# RX_FlexiConnectors.net
KiCad netlist of a schematic drawn in Altium Designer
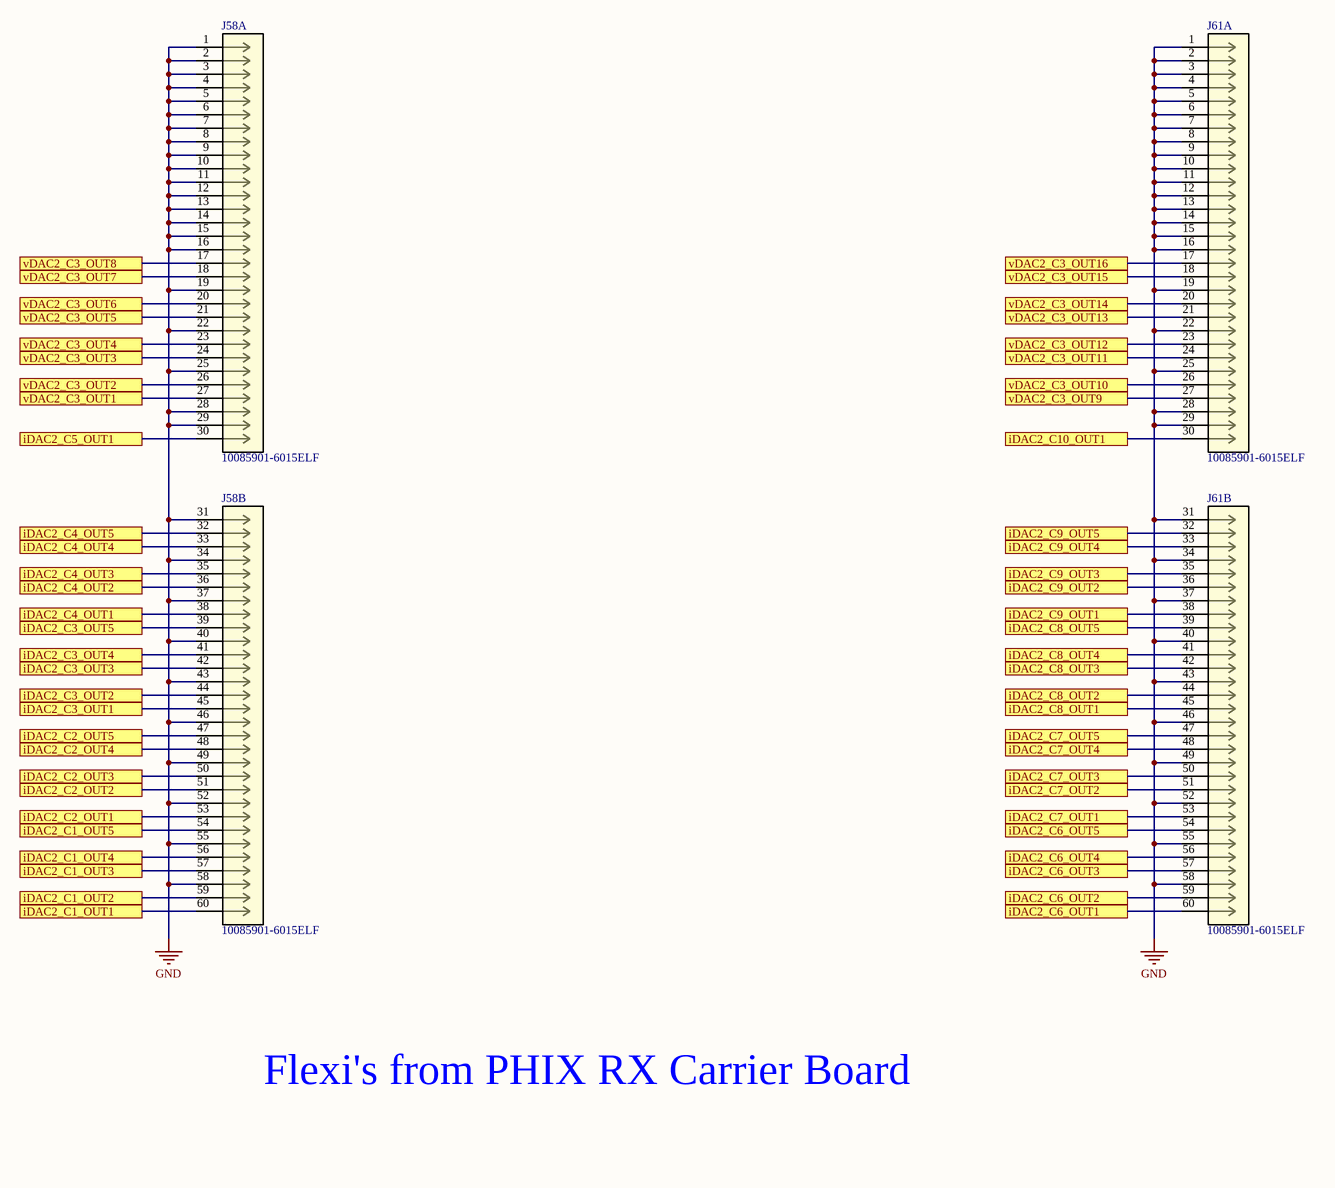
[diagram p0: RX_FlexiConnectors.SchDoc]

(export (version "E")
  (design (tool "Eeschema 10.0.6"))
  (components
    (comp (ref "J58")
      (value "10085901-6015ELF")
      (footprint "CONN_10085901-6015ELF_AMP")
      (description "No Description Available")
      (fields (field (name "COPYRIGHT") "Copyright (C) 2018 Accelerated Designs. All rights reserved"))
      (libsource (lib "PHIX-Carrier-NoDrivers") (part "10085901-6015ELF"))
    )
    (comp (ref "J61")
      (value "10085901-6015ELF")
      (footprint "CONN_10085901-6015ELF_AMP")
      (description "No Description Available")
      (fields (field (name "COPYRIGHT") "Copyright (C) 2018 Accelerated Designs. All rights reserved"))
      (libsource (lib "PHIX-Carrier-NoDrivers") (part "10085901-6015ELF"))
    )
  )
  (nets
    (net (code "1") (name "/iDAC2_C1_OUT1") (class "Default")
      (node (ref "J58") (pin "60") (pinfunction "60_60") (pintype "passive"))
    )
    (net (code "2") (name "/iDAC2_C1_OUT2") (class "Default")
      (node (ref "J58") (pin "59") (pinfunction "59_59") (pintype "passive"))
    )
    (net (code "3") (name "/iDAC2_C1_OUT3") (class "Default")
      (node (ref "J58") (pin "57") (pinfunction "57_57") (pintype "passive"))
    )
    (net (code "4") (name "/iDAC2_C1_OUT4") (class "Default")
      (node (ref "J58") (pin "56") (pinfunction "56_56") (pintype "passive"))
    )
    (net (code "5") (name "/iDAC2_C1_OUT5") (class "Default")
      (node (ref "J58") (pin "54") (pinfunction "54_54") (pintype "passive"))
    )
    (net (code "6") (name "/iDAC2_C2_OUT1") (class "Default")
      (node (ref "J58") (pin "53") (pinfunction "53_53") (pintype "passive"))
    )
    (net (code "7") (name "/iDAC2_C2_OUT2") (class "Default")
      (node (ref "J58") (pin "51") (pinfunction "51_51") (pintype "passive"))
    )
    (net (code "8") (name "/iDAC2_C2_OUT3") (class "Default")
      (node (ref "J58") (pin "50") (pinfunction "50_50") (pintype "passive"))
    )
    (net (code "9") (name "/iDAC2_C2_OUT4") (class "Default")
      (node (ref "J58") (pin "48") (pinfunction "48_48") (pintype "passive"))
    )
    (net (code "10") (name "/iDAC2_C2_OUT5") (class "Default")
      (node (ref "J58") (pin "47") (pinfunction "47_47") (pintype "passive"))
    )
    (net (code "11") (name "/iDAC2_C3_OUT1") (class "Default")
      (node (ref "J58") (pin "45") (pinfunction "45_45") (pintype "passive"))
    )
    (net (code "12") (name "/iDAC2_C3_OUT2") (class "Default")
      (node (ref "J58") (pin "44") (pinfunction "44_44") (pintype "passive"))
    )
    (net (code "13") (name "/iDAC2_C3_OUT3") (class "Default")
      (node (ref "J58") (pin "42") (pinfunction "42_42") (pintype "passive"))
    )
    (net (code "14") (name "/iDAC2_C3_OUT4") (class "Default")
      (node (ref "J58") (pin "41") (pinfunction "41_41") (pintype "passive"))
    )
    (net (code "15") (name "/iDAC2_C3_OUT5") (class "Default")
      (node (ref "J58") (pin "39") (pinfunction "39_39") (pintype "passive"))
    )
    (net (code "16") (name "/iDAC2_C4_OUT1") (class "Default")
      (node (ref "J58") (pin "38") (pinfunction "38_38") (pintype "passive"))
    )
    (net (code "17") (name "/iDAC2_C4_OUT2") (class "Default")
      (node (ref "J58") (pin "36") (pinfunction "36_36") (pintype "passive"))
    )
    (net (code "18") (name "/iDAC2_C4_OUT3") (class "Default")
      (node (ref "J58") (pin "35") (pinfunction "35_35") (pintype "passive"))
    )
    (net (code "19") (name "/iDAC2_C4_OUT4") (class "Default")
      (node (ref "J58") (pin "33") (pinfunction "33_33") (pintype "passive"))
    )
    (net (code "20") (name "/iDAC2_C4_OUT5") (class "Default")
      (node (ref "J58") (pin "32") (pinfunction "32_32") (pintype "passive"))
    )
    (net (code "21") (name "/iDAC2_C5_OUT1") (class "Default")
      (node (ref "J58") (pin "30") (pinfunction "30_30") (pintype "passive"))
    )
    (net (code "22") (name "/iDAC2_C6_OUT1") (class "Default")
      (node (ref "J61") (pin "60") (pinfunction "60_60") (pintype "passive"))
    )
    (net (code "23") (name "/iDAC2_C6_OUT2") (class "Default")
      (node (ref "J61") (pin "59") (pinfunction "59_59") (pintype "passive"))
    )
    (net (code "24") (name "/iDAC2_C6_OUT3") (class "Default")
      (node (ref "J61") (pin "57") (pinfunction "57_57") (pintype "passive"))
    )
    (net (code "25") (name "/iDAC2_C6_OUT4") (class "Default")
      (node (ref "J61") (pin "56") (pinfunction "56_56") (pintype "passive"))
    )
    (net (code "26") (name "/iDAC2_C6_OUT5") (class "Default")
      (node (ref "J61") (pin "54") (pinfunction "54_54") (pintype "passive"))
    )
    (net (code "27") (name "/iDAC2_C7_OUT1") (class "Default")
      (node (ref "J61") (pin "53") (pinfunction "53_53") (pintype "passive"))
    )
    (net (code "28") (name "/iDAC2_C7_OUT2") (class "Default")
      (node (ref "J61") (pin "51") (pinfunction "51_51") (pintype "passive"))
    )
    (net (code "29") (name "/iDAC2_C7_OUT3") (class "Default")
      (node (ref "J61") (pin "50") (pinfunction "50_50") (pintype "passive"))
    )
    (net (code "30") (name "/iDAC2_C7_OUT4") (class "Default")
      (node (ref "J61") (pin "48") (pinfunction "48_48") (pintype "passive"))
    )
    (net (code "31") (name "/iDAC2_C7_OUT5") (class "Default")
      (node (ref "J61") (pin "47") (pinfunction "47_47") (pintype "passive"))
    )
    (net (code "32") (name "/iDAC2_C8_OUT1") (class "Default")
      (node (ref "J61") (pin "45") (pinfunction "45_45") (pintype "passive"))
    )
    (net (code "33") (name "/iDAC2_C8_OUT2") (class "Default")
      (node (ref "J61") (pin "44") (pinfunction "44_44") (pintype "passive"))
    )
    (net (code "34") (name "/iDAC2_C8_OUT3") (class "Default")
      (node (ref "J61") (pin "42") (pinfunction "42_42") (pintype "passive"))
    )
    (net (code "35") (name "/iDAC2_C8_OUT4") (class "Default")
      (node (ref "J61") (pin "41") (pinfunction "41_41") (pintype "passive"))
    )
    (net (code "36") (name "/iDAC2_C8_OUT5") (class "Default")
      (node (ref "J61") (pin "39") (pinfunction "39_39") (pintype "passive"))
    )
    (net (code "37") (name "/iDAC2_C9_OUT1") (class "Default")
      (node (ref "J61") (pin "38") (pinfunction "38_38") (pintype "passive"))
    )
    (net (code "38") (name "/iDAC2_C9_OUT2") (class "Default")
      (node (ref "J61") (pin "36") (pinfunction "36_36") (pintype "passive"))
    )
    (net (code "39") (name "/iDAC2_C9_OUT3") (class "Default")
      (node (ref "J61") (pin "35") (pinfunction "35_35") (pintype "passive"))
    )
    (net (code "40") (name "/iDAC2_C9_OUT4") (class "Default")
      (node (ref "J61") (pin "33") (pinfunction "33_33") (pintype "passive"))
    )
    (net (code "41") (name "/iDAC2_C9_OUT5") (class "Default")
      (node (ref "J61") (pin "32") (pinfunction "32_32") (pintype "passive"))
    )
    (net (code "42") (name "/iDAC2_C10_OUT1") (class "Default")
      (node (ref "J61") (pin "30") (pinfunction "30_30") (pintype "passive"))
    )
    (net (code "43") (name "/vDAC2_C3_OUT1") (class "Default")
      (node (ref "J58") (pin "27") (pinfunction "27_27") (pintype "passive"))
    )
    (net (code "44") (name "/vDAC2_C3_OUT2") (class "Default")
      (node (ref "J58") (pin "26") (pinfunction "26_26") (pintype "passive"))
    )
    (net (code "45") (name "/vDAC2_C3_OUT3") (class "Default")
      (node (ref "J58") (pin "24") (pinfunction "24_24") (pintype "passive"))
    )
    (net (code "46") (name "/vDAC2_C3_OUT4") (class "Default")
      (node (ref "J58") (pin "23") (pinfunction "23_23") (pintype "passive"))
    )
    (net (code "47") (name "/vDAC2_C3_OUT5") (class "Default")
      (node (ref "J58") (pin "21") (pinfunction "21_21") (pintype "passive"))
    )
    (net (code "48") (name "/vDAC2_C3_OUT6") (class "Default")
      (node (ref "J58") (pin "20") (pinfunction "20_20") (pintype "passive"))
    )
    (net (code "49") (name "/vDAC2_C3_OUT7") (class "Default")
      (node (ref "J58") (pin "18") (pinfunction "18_18") (pintype "passive"))
    )
    (net (code "50") (name "/vDAC2_C3_OUT8") (class "Default")
      (node (ref "J58") (pin "17") (pinfunction "17_17") (pintype "passive"))
    )
    (net (code "51") (name "/vDAC2_C3_OUT9") (class "Default")
      (node (ref "J61") (pin "27") (pinfunction "27_27") (pintype "passive"))
    )
    (net (code "52") (name "/vDAC2_C3_OUT10") (class "Default")
      (node (ref "J61") (pin "26") (pinfunction "26_26") (pintype "passive"))
    )
    (net (code "53") (name "/vDAC2_C3_OUT11") (class "Default")
      (node (ref "J61") (pin "24") (pinfunction "24_24") (pintype "passive"))
    )
    (net (code "54") (name "/vDAC2_C3_OUT12") (class "Default")
      (node (ref "J61") (pin "23") (pinfunction "23_23") (pintype "passive"))
    )
    (net (code "55") (name "/vDAC2_C3_OUT13") (class "Default")
      (node (ref "J61") (pin "21") (pinfunction "21_21") (pintype "passive"))
    )
    (net (code "56") (name "/vDAC2_C3_OUT14") (class "Default")
      (node (ref "J61") (pin "20") (pinfunction "20_20") (pintype "passive"))
    )
    (net (code "57") (name "/vDAC2_C3_OUT15") (class "Default")
      (node (ref "J61") (pin "18") (pinfunction "18_18") (pintype "passive"))
    )
    (net (code "58") (name "/vDAC2_C3_OUT16") (class "Default")
      (node (ref "J61") (pin "17") (pinfunction "17_17") (pintype "passive"))
    )
    (net (code "59") (name "GND") (class "Default")
      (node (ref "J58") (pin "1") (pinfunction "1_1") (pintype "passive"))
      (node (ref "J58") (pin "10") (pinfunction "10_10") (pintype "passive"))
      (node (ref "J58") (pin "11") (pinfunction "11_11") (pintype "passive"))
      (node (ref "J58") (pin "12") (pinfunction "12_12") (pintype "passive"))
      (node (ref "J58") (pin "13") (pinfunction "13_13") (pintype "passive"))
      (node (ref "J58") (pin "14") (pinfunction "14_14") (pintype "passive"))
      (node (ref "J58") (pin "15") (pinfunction "15_15") (pintype "passive"))
      (node (ref "J58") (pin "16") (pinfunction "16_16") (pintype "passive"))
      (node (ref "J58") (pin "19") (pinfunction "19_19") (pintype "passive"))
      (node (ref "J58") (pin "2") (pinfunction "2_2") (pintype "passive"))
      (node (ref "J58") (pin "22") (pinfunction "22_22") (pintype "passive"))
      (node (ref "J58") (pin "25") (pinfunction "25_25") (pintype "passive"))
      (node (ref "J58") (pin "28") (pinfunction "28_28") (pintype "passive"))
      (node (ref "J58") (pin "29") (pinfunction "29_29") (pintype "passive"))
      (node (ref "J58") (pin "3") (pinfunction "3_3") (pintype "passive"))
      (node (ref "J58") (pin "31") (pinfunction "31_31") (pintype "passive"))
      (node (ref "J58") (pin "34") (pinfunction "34_34") (pintype "passive"))
      (node (ref "J58") (pin "37") (pinfunction "37_37") (pintype "passive"))
      (node (ref "J58") (pin "4") (pinfunction "4_4") (pintype "passive"))
      (node (ref "J58") (pin "40") (pinfunction "40_40") (pintype "passive"))
      (node (ref "J58") (pin "43") (pinfunction "43_43") (pintype "passive"))
      (node (ref "J58") (pin "46") (pinfunction "46_46") (pintype "passive"))
      (node (ref "J58") (pin "49") (pinfunction "49_49") (pintype "passive"))
      (node (ref "J58") (pin "5") (pinfunction "5_5") (pintype "passive"))
      (node (ref "J58") (pin "52") (pinfunction "52_52") (pintype "passive"))
      (node (ref "J58") (pin "55") (pinfunction "55_55") (pintype "passive"))
      (node (ref "J58") (pin "58") (pinfunction "58_58") (pintype "passive"))
      (node (ref "J58") (pin "6") (pinfunction "6_6") (pintype "passive"))
      (node (ref "J58") (pin "7") (pinfunction "7_7") (pintype "passive"))
      (node (ref "J58") (pin "8") (pinfunction "8_8") (pintype "passive"))
      (node (ref "J58") (pin "9") (pinfunction "9_9") (pintype "passive"))
      (node (ref "J61") (pin "1") (pinfunction "1_1") (pintype "passive"))
      (node (ref "J61") (pin "10") (pinfunction "10_10") (pintype "passive"))
      (node (ref "J61") (pin "11") (pinfunction "11_11") (pintype "passive"))
      (node (ref "J61") (pin "12") (pinfunction "12_12") (pintype "passive"))
      (node (ref "J61") (pin "13") (pinfunction "13_13") (pintype "passive"))
      (node (ref "J61") (pin "14") (pinfunction "14_14") (pintype "passive"))
      (node (ref "J61") (pin "15") (pinfunction "15_15") (pintype "passive"))
      (node (ref "J61") (pin "16") (pinfunction "16_16") (pintype "passive"))
      (node (ref "J61") (pin "19") (pinfunction "19_19") (pintype "passive"))
      (node (ref "J61") (pin "2") (pinfunction "2_2") (pintype "passive"))
      (node (ref "J61") (pin "22") (pinfunction "22_22") (pintype "passive"))
      (node (ref "J61") (pin "25") (pinfunction "25_25") (pintype "passive"))
      (node (ref "J61") (pin "28") (pinfunction "28_28") (pintype "passive"))
      (node (ref "J61") (pin "29") (pinfunction "29_29") (pintype "passive"))
      (node (ref "J61") (pin "3") (pinfunction "3_3") (pintype "passive"))
      (node (ref "J61") (pin "31") (pinfunction "31_31") (pintype "passive"))
      (node (ref "J61") (pin "34") (pinfunction "34_34") (pintype "passive"))
      (node (ref "J61") (pin "37") (pinfunction "37_37") (pintype "passive"))
      (node (ref "J61") (pin "4") (pinfunction "4_4") (pintype "passive"))
      (node (ref "J61") (pin "40") (pinfunction "40_40") (pintype "passive"))
      (node (ref "J61") (pin "43") (pinfunction "43_43") (pintype "passive"))
      (node (ref "J61") (pin "46") (pinfunction "46_46") (pintype "passive"))
      (node (ref "J61") (pin "49") (pinfunction "49_49") (pintype "passive"))
      (node (ref "J61") (pin "5") (pinfunction "5_5") (pintype "passive"))
      (node (ref "J61") (pin "52") (pinfunction "52_52") (pintype "passive"))
      (node (ref "J61") (pin "55") (pinfunction "55_55") (pintype "passive"))
      (node (ref "J61") (pin "58") (pinfunction "58_58") (pintype "passive"))
      (node (ref "J61") (pin "6") (pinfunction "6_6") (pintype "passive"))
      (node (ref "J61") (pin "7") (pinfunction "7_7") (pintype "passive"))
      (node (ref "J61") (pin "8") (pinfunction "8_8") (pintype "passive"))
      (node (ref "J61") (pin "9") (pinfunction "9_9") (pintype "passive"))
    )
  )
)
